# DDR4_SODIMM_PWR.net
KiCad netlist of a schematic drawn in Altium Designer
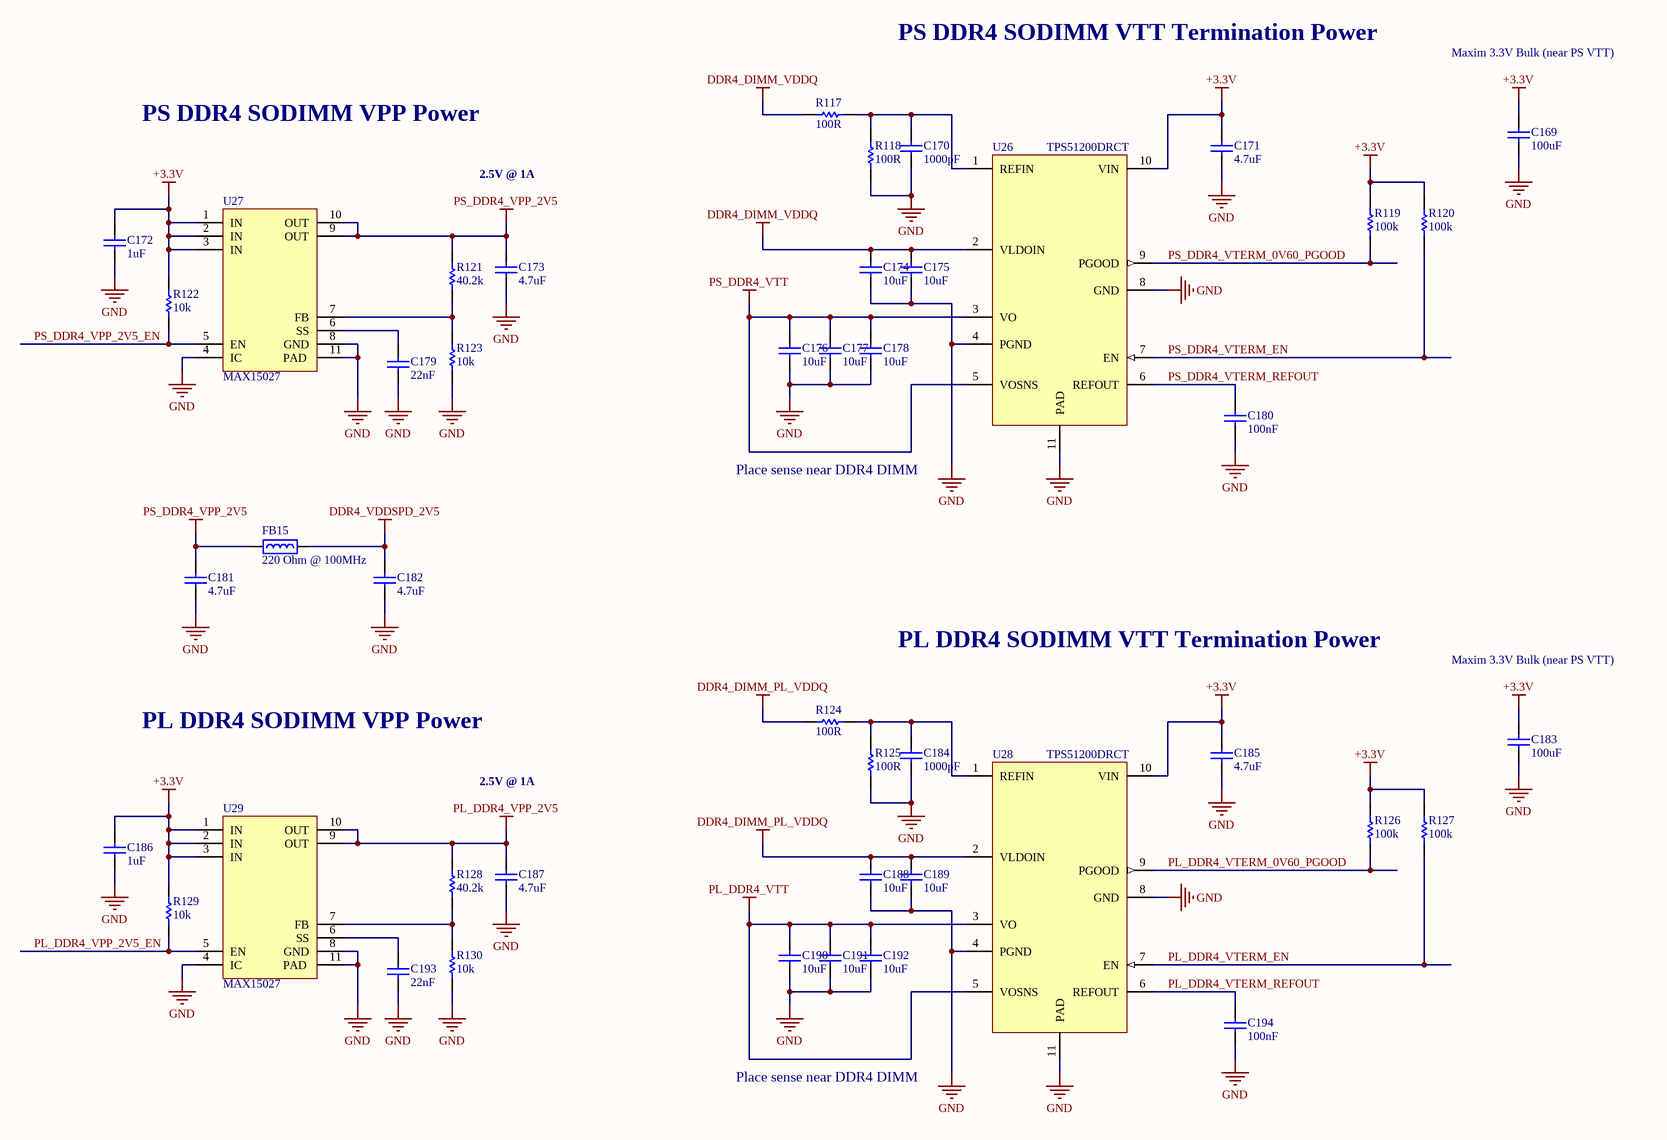
[diagram p0: DDR4_SODIMM_PWR.SchDoc]

(export (version "E")
  (design (tool "Eeschema 10.0.6"))
  (components
    (comp (ref "C169")
      (value "100uF")
      (footprint "CAPC3225N_1210")
      (description "CAP CER 100UF 16V X5R 1210")
      (fields (field (name "VOLTAGE") "16V") (field (name "TOLERANCE") "20%"))
      (libsource (lib "Ultrascale_SchLib") (part "CAPCER1210X5R100U16V_20T"))
    )
    (comp (ref "C170")
      (value "1000pF")
      (footprint "CAPC1005L_0402")
      (description "CAP CER 1000PF 50V X7R 0402")
      (fields (field (name "VOLTAGE") "50V") (field (name "TOLERANCE") "10%"))
      (libsource (lib "Ultrascale_SchLib") (part "CAPCER0402X7R1000P50V_10T"))
    )
    (comp (ref "C171")
      (value "4.7uF")
      (footprint "CAPC1005L_0402")
      (description "CAP CER 4.7UF 10V X5R 0402")
      (fields (field (name "VOLTAGE") "10V") (field (name "TOLERANCE") "10%"))
      (libsource (lib "Ultrascale_SchLib") (part "CAPCER0402X5R4U710V_10T"))
    )
    (comp (ref "C172")
      (value "1uF")
      (footprint "CAPC1005L_0402")
      (description "CAP CER 1UF 16V X5R 0402")
      (fields (field (name "VOLTAGE") "16V") (field (name "TOLERANCE") "20%"))
      (libsource (lib "Ultrascale_SchLib") (part "CAPCER0402X5R1U16V_20T"))
    )
    (comp (ref "C173")
      (value "4.7uF")
      (footprint "CAPC1005L_0402")
      (description "CAP CER 4.7UF 10V X5R 0402")
      (fields (field (name "VOLTAGE") "10V") (field (name "TOLERANCE") "10%"))
      (libsource (lib "Ultrascale_SchLib") (part "CAPCER0402X5R4U710V_10T"))
    )
    (comp (ref "C174")
      (value "10uF")
      (footprint "CAPC1005L_0402")
      (description "CAP CER 10UF 10V X5R 0402")
      (fields (field (name "VOLTAGE") "10V") (field (name "TOLERANCE") "20%"))
      (libsource (lib "Ultrascale_SchLib") (part "CAPCER0402X5R10U10V_20T"))
    )
    (comp (ref "C175")
      (value "10uF")
      (footprint "CAPC1005L_0402")
      (description "CAP CER 10UF 10V X5R 0402")
      (fields (field (name "VOLTAGE") "10V") (field (name "TOLERANCE") "20%"))
      (libsource (lib "Ultrascale_SchLib") (part "CAPCER0402X5R10U10V_20T"))
    )
    (comp (ref "C176")
      (value "10uF")
      (footprint "CAPC1005L_0402")
      (description "CAP CER 10UF 10V X5R 0402")
      (fields (field (name "VOLTAGE") "10V") (field (name "TOLERANCE") "20%"))
      (libsource (lib "Ultrascale_SchLib") (part "CAPCER0402X5R10U10V_20T"))
    )
    (comp (ref "C177")
      (value "10uF")
      (footprint "CAPC1005L_0402")
      (description "CAP CER 10UF 10V X5R 0402")
      (fields (field (name "VOLTAGE") "10V") (field (name "TOLERANCE") "20%"))
      (libsource (lib "Ultrascale_SchLib") (part "CAPCER0402X5R10U10V_20T"))
    )
    (comp (ref "C178")
      (value "10uF")
      (footprint "CAPC1005L_0402")
      (description "CAP CER 10UF 10V X5R 0402")
      (fields (field (name "VOLTAGE") "10V") (field (name "TOLERANCE") "20%"))
      (libsource (lib "Ultrascale_SchLib") (part "CAPCER0402X5R10U10V_20T"))
    )
    (comp (ref "C179")
      (value "22nF")
      (footprint "CAPC1005L_0402")
      (description "CAP CER 0.022UF 50V X7R 0402")
      (fields (field (name "VOLTAGE") "50V") (field (name "TOLERANCE") "10%"))
      (libsource (lib "Ultrascale_SchLib") (part "CAPCER0402X7R22N50V_10T"))
    )
    (comp (ref "C180")
      (value "100nF")
      (footprint "CAPC1005L_0402")
      (description "CAP CER 0.1UF 25V X7R 0402")
      (fields (field (name "VOLTAGE") "25V") (field (name "TOLERANCE") "10%"))
      (libsource (lib "Ultrascale_SchLib") (part "CAPCER0402X7R100N25V_10T"))
    )
    (comp (ref "C181")
      (value "4.7uF")
      (footprint "CAPC1005L_0402")
      (description "CAP CER 4.7UF 10V X5R 0402")
      (fields (field (name "VOLTAGE") "10V") (field (name "TOLERANCE") "10%"))
      (libsource (lib "Ultrascale_SchLib") (part "CAPCER0402X5R4U710V_10T"))
    )
    (comp (ref "C182")
      (value "4.7uF")
      (footprint "CAPC1005L_0402")
      (description "CAP CER 4.7UF 10V X5R 0402")
      (fields (field (name "VOLTAGE") "10V") (field (name "TOLERANCE") "10%"))
      (libsource (lib "Ultrascale_SchLib") (part "CAPCER0402X5R4U710V_10T"))
    )
    (comp (ref "C183")
      (value "100uF")
      (footprint "CAPC3225N_1210")
      (description "CAP CER 100UF 16V X5R 1210")
      (fields (field (name "VOLTAGE") "16V") (field (name "TOLERANCE") "20%"))
      (libsource (lib "Ultrascale_SchLib") (part "CAPCER1210X5R100U16V_20T"))
    )
    (comp (ref "C184")
      (value "1000pF")
      (footprint "CAPC1005L_0402")
      (description "CAP CER 1000PF 50V X7R 0402")
      (fields (field (name "VOLTAGE") "50V") (field (name "TOLERANCE") "10%"))
      (libsource (lib "Ultrascale_SchLib") (part "CAPCER0402X7R1000P50V_10T"))
    )
    (comp (ref "C185")
      (value "4.7uF")
      (footprint "CAPC1005L_0402")
      (description "CAP CER 4.7UF 10V X5R 0402")
      (fields (field (name "VOLTAGE") "10V") (field (name "TOLERANCE") "10%"))
      (libsource (lib "Ultrascale_SchLib") (part "CAPCER0402X5R4U710V_10T"))
    )
    (comp (ref "C186")
      (value "1uF")
      (footprint "CAPC1005L_0402")
      (description "CAP CER 1UF 16V X5R 0402")
      (fields (field (name "VOLTAGE") "16V") (field (name "TOLERANCE") "20%"))
      (libsource (lib "Ultrascale_SchLib") (part "CAPCER0402X5R1U16V_20T"))
    )
    (comp (ref "C187")
      (value "4.7uF")
      (footprint "CAPC1005L_0402")
      (description "CAP CER 4.7UF 10V X5R 0402")
      (fields (field (name "VOLTAGE") "10V") (field (name "TOLERANCE") "10%"))
      (libsource (lib "Ultrascale_SchLib") (part "CAPCER0402X5R4U710V_10T"))
    )
    (comp (ref "C188")
      (value "10uF")
      (footprint "CAPC1005L_0402")
      (description "CAP CER 10UF 10V X5R 0402")
      (fields (field (name "VOLTAGE") "10V") (field (name "TOLERANCE") "20%"))
      (libsource (lib "Ultrascale_SchLib") (part "CAPCER0402X5R10U10V_20T"))
    )
    (comp (ref "C189")
      (value "10uF")
      (footprint "CAPC1005L_0402")
      (description "CAP CER 10UF 10V X5R 0402")
      (fields (field (name "VOLTAGE") "10V") (field (name "TOLERANCE") "20%"))
      (libsource (lib "Ultrascale_SchLib") (part "CAPCER0402X5R10U10V_20T"))
    )
    (comp (ref "C190")
      (value "10uF")
      (footprint "CAPC1005L_0402")
      (description "CAP CER 10UF 10V X5R 0402")
      (fields (field (name "VOLTAGE") "10V") (field (name "TOLERANCE") "20%"))
      (libsource (lib "Ultrascale_SchLib") (part "CAPCER0402X5R10U10V_20T"))
    )
    (comp (ref "C191")
      (value "10uF")
      (footprint "CAPC1005L_0402")
      (description "CAP CER 10UF 10V X5R 0402")
      (fields (field (name "VOLTAGE") "10V") (field (name "TOLERANCE") "20%"))
      (libsource (lib "Ultrascale_SchLib") (part "CAPCER0402X5R10U10V_20T"))
    )
    (comp (ref "C192")
      (value "10uF")
      (footprint "CAPC1005L_0402")
      (description "CAP CER 10UF 10V X5R 0402")
      (fields (field (name "VOLTAGE") "10V") (field (name "TOLERANCE") "20%"))
      (libsource (lib "Ultrascale_SchLib") (part "CAPCER0402X5R10U10V_20T"))
    )
    (comp (ref "C193")
      (value "22nF")
      (footprint "CAPC1005L_0402")
      (description "CAP CER 0.022UF 50V X7R 0402")
      (fields (field (name "VOLTAGE") "50V") (field (name "TOLERANCE") "10%"))
      (libsource (lib "Ultrascale_SchLib") (part "CAPCER0402X7R22N50V_10T"))
    )
    (comp (ref "C194")
      (value "100nF")
      (footprint "CAPC1005L_0402")
      (description "CAP CER 0.1UF 25V X7R 0402")
      (fields (field (name "VOLTAGE") "25V") (field (name "TOLERANCE") "10%"))
      (libsource (lib "Ultrascale_SchLib") (part "CAPCER0402X7R100N25V_10T"))
    )
    (comp (ref "FB15")
      (value "BEAD0603_220_2A5_40M")
      (footprint "INDC1608N_0603")
      (description "FERRITE BEAD 220 OHM 0603 1LN")
      (fields (field (name "IMPEDANCE @ FREQUENCY") "220 Ohm @ 100MHz"))
      (libsource (lib "Ultrascale_SchLib") (part "BEAD0603_220_2A5_40M"))
    )
    (comp (ref "R117")
      (value "100R")
      (footprint "RESC1005L_0402")
      (description "RES SMD 100 OHM 1% 1/10W 0402")
      (fields (field (name "POWER") "1/10W") (field (name "TOLERANCE") "1%"))
      (libsource (lib "Ultrascale_SchLib") (part "RES0402_100R_0W1_1T"))
    )
    (comp (ref "R118")
      (value "100R")
      (footprint "RESC1005L_0402")
      (description "RES SMD 100 OHM 1% 1/10W 0402")
      (fields (field (name "POWER") "1/10W") (field (name "TOLERANCE") "1%"))
      (libsource (lib "Ultrascale_SchLib") (part "RES0402_100R_0W1_1T"))
    )
    (comp (ref "R119")
      (value "100k")
      (footprint "RESC1005L_0402")
      (description "RES SMD 100K OHM 1% 1/5W 0402")
      (fields (field (name "POWER") "1/5W") (field (name "TOLERANCE") "1%"))
      (libsource (lib "Ultrascale_SchLib") (part "RES0402_100K_0W2_1T"))
    )
    (comp (ref "R120")
      (value "100k")
      (footprint "RESC1005L_0402")
      (description "RES SMD 100K OHM 1% 1/5W 0402")
      (fields (field (name "POWER") "1/5W") (field (name "TOLERANCE") "1%"))
      (libsource (lib "Ultrascale_SchLib") (part "RES0402_100K_0W2_1T"))
    )
    (comp (ref "R121")
      (value "40.2k")
      (footprint "RESC1005L_0402")
      (description "RES SMD 40.2K OHM 1% 1/10W 0402")
      (fields (field (name "POWER") "1/10W") (field (name "TOLERANCE") "1%"))
      (libsource (lib "Ultrascale_SchLib") (part "RES0402_40K2_0W1_1T"))
    )
    (comp (ref "R122")
      (value "10k")
      (footprint "RESC1005L_0402")
      (description "RES SMD 10K OHM 0.5% 1/16W 0402")
      (fields (field (name "POWER") "1/16W") (field (name "TOLERANCE") "0.5%"))
      (libsource (lib "Ultrascale_SchLib") (part "RES0402_10K_0W1_05T"))
    )
    (comp (ref "R123")
      (value "10k")
      (footprint "RESC1005L_0402")
      (description "RES SMD 10K OHM 0.5% 1/16W 0402")
      (fields (field (name "POWER") "1/16W") (field (name "TOLERANCE") "0.5%"))
      (libsource (lib "Ultrascale_SchLib") (part "RES0402_10K_0W1_05T"))
    )
    (comp (ref "R124")
      (value "100R")
      (footprint "RESC1005L_0402")
      (description "RES SMD 100 OHM 1% 1/10W 0402")
      (fields (field (name "POWER") "1/10W") (field (name "TOLERANCE") "1%"))
      (libsource (lib "Ultrascale_SchLib") (part "RES0402_100R_0W1_1T"))
    )
    (comp (ref "R125")
      (value "100R")
      (footprint "RESC1005L_0402")
      (description "RES SMD 100 OHM 1% 1/10W 0402")
      (fields (field (name "POWER") "1/10W") (field (name "TOLERANCE") "1%"))
      (libsource (lib "Ultrascale_SchLib") (part "RES0402_100R_0W1_1T"))
    )
    (comp (ref "R126")
      (value "100k")
      (footprint "RESC1005L_0402")
      (description "RES SMD 100K OHM 1% 1/5W 0402")
      (fields (field (name "POWER") "1/5W") (field (name "TOLERANCE") "1%"))
      (libsource (lib "Ultrascale_SchLib") (part "RES0402_100K_0W2_1T"))
    )
    (comp (ref "R127")
      (value "100k")
      (footprint "RESC1005L_0402")
      (description "RES SMD 100K OHM 1% 1/5W 0402")
      (fields (field (name "POWER") "1/5W") (field (name "TOLERANCE") "1%"))
      (libsource (lib "Ultrascale_SchLib") (part "RES0402_100K_0W2_1T"))
    )
    (comp (ref "R128")
      (value "40.2k")
      (footprint "RESC1005L_0402")
      (description "RES SMD 40.2K OHM 1% 1/10W 0402")
      (fields (field (name "POWER") "1/10W") (field (name "TOLERANCE") "1%"))
      (libsource (lib "Ultrascale_SchLib") (part "RES0402_40K2_0W1_1T"))
    )
    (comp (ref "R129")
      (value "10k")
      (footprint "RESC1005L_0402")
      (description "RES SMD 10K OHM 0.5% 1/16W 0402")
      (fields (field (name "POWER") "1/16W") (field (name "TOLERANCE") "0.5%"))
      (libsource (lib "Ultrascale_SchLib") (part "RES0402_10K_0W1_05T"))
    )
    (comp (ref "R130")
      (value "10k")
      (footprint "RESC1005L_0402")
      (description "RES SMD 10K OHM 0.5% 1/16W 0402")
      (fields (field (name "POWER") "1/16W") (field (name "TOLERANCE") "0.5%"))
      (libsource (lib "Ultrascale_SchLib") (part "RES0402_10K_0W1_05T"))
    )
    (comp (ref "U26")
      (value "TPS51200DRCT")
      (footprint "DRC_S-PVSON-N10")
      (description "IC SINK/SOURCE DDR REG 10-SON")
      (libsource (lib "Ultrascale_SchLib") (part "TPS51200DRCT"))
    )
    (comp (ref "U27")
      (value "MAX15027")
      (footprint "MAX15027_T1033+1_V")
      (description "IC REG LINEAR POS ADJ 1A 10TDFN")
      (libsource (lib "Ultrascale_SchLib") (part "MAX15027"))
    )
    (comp (ref "U28")
      (value "TPS51200DRCT")
      (footprint "DRC_S-PVSON-N10")
      (description "IC SINK/SOURCE DDR REG 10-SON")
      (libsource (lib "Ultrascale_SchLib") (part "TPS51200DRCT"))
    )
    (comp (ref "U29")
      (value "MAX15027")
      (footprint "MAX15027_T1033+1_V")
      (description "IC REG LINEAR POS ADJ 1A 10TDFN")
      (libsource (lib "Ultrascale_SchLib") (part "MAX15027"))
    )
  )
  (nets
    (net (code "1") (name "+3.3V") (class "Default")
      (node (ref "C169") (pin "2") (pinfunction "2_2") (pintype "passive"))
      (node (ref "C171") (pin "2") (pinfunction "2_2") (pintype "passive"))
      (node (ref "C172") (pin "2") (pinfunction "2_2") (pintype "passive"))
      (node (ref "C183") (pin "2") (pinfunction "2_2") (pintype "passive"))
      (node (ref "C185") (pin "2") (pinfunction "2_2") (pintype "passive"))
      (node (ref "C186") (pin "2") (pinfunction "2_2") (pintype "passive"))
      (node (ref "R119") (pin "2") (pinfunction "2_2") (pintype "passive"))
      (node (ref "R120") (pin "2") (pinfunction "2_2") (pintype "passive"))
      (node (ref "R122") (pin "2") (pinfunction "2_2") (pintype "passive"))
      (node (ref "R126") (pin "2") (pinfunction "2_2") (pintype "passive"))
      (node (ref "R127") (pin "2") (pinfunction "2_2") (pintype "passive"))
      (node (ref "R129") (pin "2") (pinfunction "2_2") (pintype "passive"))
      (node (ref "U26") (pin "10") (pinfunction "VIN_10") (pintype "passive"))
      (node (ref "U27") (pin "1") (pinfunction "IN_1") (pintype "passive"))
      (node (ref "U27") (pin "2") (pinfunction "IN_2") (pintype "passive"))
      (node (ref "U27") (pin "3") (pinfunction "IN_3") (pintype "passive"))
      (node (ref "U28") (pin "10") (pinfunction "VIN_10") (pintype "passive"))
      (node (ref "U29") (pin "1") (pinfunction "IN_1") (pintype "passive"))
      (node (ref "U29") (pin "2") (pinfunction "IN_2") (pintype "passive"))
      (node (ref "U29") (pin "3") (pinfunction "IN_3") (pintype "passive"))
    )
    (net (code "2") (name "/PL_DDR4_VPP_2V5_EN") (class "Default")
      (node (ref "R129") (pin "1") (pinfunction "1_1") (pintype "passive"))
      (node (ref "U29") (pin "5") (pinfunction "EN_5") (pintype "passive"))
    )
    (net (code "3") (name "/PL_DDR4_VTERM_0V60_PGOOD") (class "Default")
      (node (ref "R126") (pin "1") (pinfunction "1_1") (pintype "passive"))
      (node (ref "U28") (pin "9") (pinfunction "PGOOD_9") (pintype "output"))
    )
    (net (code "4") (name "/PL_DDR4_VTERM_EN") (class "Default")
      (node (ref "R127") (pin "1") (pinfunction "1_1") (pintype "passive"))
      (node (ref "U28") (pin "7") (pinfunction "EN_7") (pintype "input"))
    )
    (net (code "5") (name "/PL_DDR4_VTERM_REFOUT") (class "Default")
      (node (ref "C194") (pin "2") (pinfunction "2_2") (pintype "passive"))
      (node (ref "U28") (pin "6") (pinfunction "REFOUT_6") (pintype "passive"))
    )
    (net (code "6") (name "/PS_DDR4_VPP_2V5_EN") (class "Default")
      (node (ref "R122") (pin "1") (pinfunction "1_1") (pintype "passive"))
      (node (ref "U27") (pin "5") (pinfunction "EN_5") (pintype "passive"))
    )
    (net (code "7") (name "/PS_DDR4_VTERM_0V60_PGOOD") (class "Default")
      (node (ref "R119") (pin "1") (pinfunction "1_1") (pintype "passive"))
      (node (ref "U26") (pin "9") (pinfunction "PGOOD_9") (pintype "output"))
    )
    (net (code "8") (name "/PS_DDR4_VTERM_EN") (class "Default")
      (node (ref "R120") (pin "1") (pinfunction "1_1") (pintype "passive"))
      (node (ref "U26") (pin "7") (pinfunction "EN_7") (pintype "input"))
    )
    (net (code "9") (name "/PS_DDR4_VTERM_REFOUT") (class "Default")
      (node (ref "C180") (pin "2") (pinfunction "2_2") (pintype "passive"))
      (node (ref "U26") (pin "6") (pinfunction "REFOUT_6") (pintype "passive"))
    )
    (net (code "10") (name "DDR4_DIMM_PL_VDDQ") (class "Default")
      (node (ref "C188") (pin "2") (pinfunction "2_2") (pintype "passive"))
      (node (ref "C189") (pin "2") (pinfunction "2_2") (pintype "passive"))
      (node (ref "R124") (pin "2") (pinfunction "2_2") (pintype "passive"))
      (node (ref "U28") (pin "2") (pinfunction "VLDOIN_2") (pintype "passive"))
    )
    (net (code "11") (name "DDR4_DIMM_VDDQ") (class "Default")
      (node (ref "C174") (pin "2") (pinfunction "2_2") (pintype "passive"))
      (node (ref "C175") (pin "2") (pinfunction "2_2") (pintype "passive"))
      (node (ref "R117") (pin "2") (pinfunction "2_2") (pintype "passive"))
      (node (ref "U26") (pin "2") (pinfunction "VLDOIN_2") (pintype "passive"))
    )
    (net (code "12") (name "DDR4_VDDSPD_2V5") (class "Default")
      (node (ref "C182") (pin "2") (pinfunction "2_2") (pintype "passive"))
      (node (ref "FB15") (pin "2") (pinfunction "2_2") (pintype "passive"))
    )
    (net (code "13") (name "GND") (class "Default")
      (node (ref "C169") (pin "1") (pinfunction "1_1") (pintype "passive"))
      (node (ref "C170") (pin "1") (pinfunction "1_1") (pintype "passive"))
      (node (ref "C171") (pin "1") (pinfunction "1_1") (pintype "passive"))
      (node (ref "C172") (pin "1") (pinfunction "1_1") (pintype "passive"))
      (node (ref "C173") (pin "1") (pinfunction "1_1") (pintype "passive"))
      (node (ref "C174") (pin "1") (pinfunction "1_1") (pintype "passive"))
      (node (ref "C175") (pin "1") (pinfunction "1_1") (pintype "passive"))
      (node (ref "C176") (pin "1") (pinfunction "1_1") (pintype "passive"))
      (node (ref "C177") (pin "1") (pinfunction "1_1") (pintype "passive"))
      (node (ref "C178") (pin "1") (pinfunction "1_1") (pintype "passive"))
      (node (ref "C179") (pin "1") (pinfunction "1_1") (pintype "passive"))
      (node (ref "C180") (pin "1") (pinfunction "1_1") (pintype "passive"))
      (node (ref "C181") (pin "1") (pinfunction "1_1") (pintype "passive"))
      (node (ref "C182") (pin "1") (pinfunction "1_1") (pintype "passive"))
      (node (ref "C183") (pin "1") (pinfunction "1_1") (pintype "passive"))
      (node (ref "C184") (pin "1") (pinfunction "1_1") (pintype "passive"))
      (node (ref "C185") (pin "1") (pinfunction "1_1") (pintype "passive"))
      (node (ref "C186") (pin "1") (pinfunction "1_1") (pintype "passive"))
      (node (ref "C187") (pin "1") (pinfunction "1_1") (pintype "passive"))
      (node (ref "C188") (pin "1") (pinfunction "1_1") (pintype "passive"))
      (node (ref "C189") (pin "1") (pinfunction "1_1") (pintype "passive"))
      (node (ref "C190") (pin "1") (pinfunction "1_1") (pintype "passive"))
      (node (ref "C191") (pin "1") (pinfunction "1_1") (pintype "passive"))
      (node (ref "C192") (pin "1") (pinfunction "1_1") (pintype "passive"))
      (node (ref "C193") (pin "1") (pinfunction "1_1") (pintype "passive"))
      (node (ref "C194") (pin "1") (pinfunction "1_1") (pintype "passive"))
      (node (ref "R118") (pin "2") (pinfunction "2_2") (pintype "passive"))
      (node (ref "R123") (pin "1") (pinfunction "1_1") (pintype "passive"))
      (node (ref "R125") (pin "2") (pinfunction "2_2") (pintype "passive"))
      (node (ref "R130") (pin "1") (pinfunction "1_1") (pintype "passive"))
      (node (ref "U26") (pin "11") (pinfunction "PAD_11") (pintype "passive"))
      (node (ref "U26") (pin "4") (pinfunction "PGND_4") (pintype "passive"))
      (node (ref "U26") (pin "8") (pinfunction "GND_8") (pintype "passive"))
      (node (ref "U27") (pin "11") (pinfunction "PAD_11") (pintype "passive"))
      (node (ref "U27") (pin "4") (pinfunction "IC_4") (pintype "passive"))
      (node (ref "U27") (pin "8") (pinfunction "GND_8") (pintype "passive"))
      (node (ref "U28") (pin "11") (pinfunction "PAD_11") (pintype "passive"))
      (node (ref "U28") (pin "4") (pinfunction "PGND_4") (pintype "passive"))
      (node (ref "U28") (pin "8") (pinfunction "GND_8") (pintype "passive"))
      (node (ref "U29") (pin "11") (pinfunction "PAD_11") (pintype "passive"))
      (node (ref "U29") (pin "4") (pinfunction "IC_4") (pintype "passive"))
      (node (ref "U29") (pin "8") (pinfunction "GND_8") (pintype "passive"))
    )
    (net (code "14") (name "Net-(U26-REFIN)") (class "Default")
      (node (ref "C170") (pin "2") (pinfunction "2_2") (pintype "passive"))
      (node (ref "R117") (pin "1") (pinfunction "1_1") (pintype "passive"))
      (node (ref "R118") (pin "1") (pinfunction "1_1") (pintype "passive"))
      (node (ref "U26") (pin "1") (pinfunction "REFIN_1") (pintype "passive"))
    )
    (net (code "15") (name "Net-(U27-FB)") (class "Default")
      (node (ref "R121") (pin "1") (pinfunction "1_1") (pintype "passive"))
      (node (ref "R123") (pin "2") (pinfunction "2_2") (pintype "passive"))
      (node (ref "U27") (pin "7") (pinfunction "FB_7") (pintype "passive"))
    )
    (net (code "16") (name "Net-(U27-SS)") (class "Default")
      (node (ref "C179") (pin "2") (pinfunction "2_2") (pintype "passive"))
      (node (ref "U27") (pin "6") (pinfunction "SS_6") (pintype "passive"))
    )
    (net (code "17") (name "Net-(U28-REFIN)") (class "Default")
      (node (ref "C184") (pin "2") (pinfunction "2_2") (pintype "passive"))
      (node (ref "R124") (pin "1") (pinfunction "1_1") (pintype "passive"))
      (node (ref "R125") (pin "1") (pinfunction "1_1") (pintype "passive"))
      (node (ref "U28") (pin "1") (pinfunction "REFIN_1") (pintype "passive"))
    )
    (net (code "18") (name "Net-(U29-FB)") (class "Default")
      (node (ref "R128") (pin "1") (pinfunction "1_1") (pintype "passive"))
      (node (ref "R130") (pin "2") (pinfunction "2_2") (pintype "passive"))
      (node (ref "U29") (pin "7") (pinfunction "FB_7") (pintype "passive"))
    )
    (net (code "19") (name "Net-(U29-SS)") (class "Default")
      (node (ref "C193") (pin "2") (pinfunction "2_2") (pintype "passive"))
      (node (ref "U29") (pin "6") (pinfunction "SS_6") (pintype "passive"))
    )
    (net (code "20") (name "PL_DDR4_VPP_2V5") (class "Default")
      (node (ref "C187") (pin "2") (pinfunction "2_2") (pintype "passive"))
      (node (ref "R128") (pin "2") (pinfunction "2_2") (pintype "passive"))
      (node (ref "U29") (pin "10") (pinfunction "OUT_10") (pintype "passive"))
      (node (ref "U29") (pin "9") (pinfunction "OUT_9") (pintype "passive"))
    )
    (net (code "21") (name "PL_DDR4_VTT") (class "Default")
      (node (ref "C190") (pin "2") (pinfunction "2_2") (pintype "passive"))
      (node (ref "C191") (pin "2") (pinfunction "2_2") (pintype "passive"))
      (node (ref "C192") (pin "2") (pinfunction "2_2") (pintype "passive"))
      (node (ref "U28") (pin "3") (pinfunction "VO_3") (pintype "passive"))
      (node (ref "U28") (pin "5") (pinfunction "VOSNS_5") (pintype "passive"))
    )
    (net (code "22") (name "PS_DDR4_VPP_2V5") (class "Default")
      (node (ref "C173") (pin "2") (pinfunction "2_2") (pintype "passive"))
      (node (ref "C181") (pin "2") (pinfunction "2_2") (pintype "passive"))
      (node (ref "FB15") (pin "1") (pinfunction "1_1") (pintype "passive"))
      (node (ref "R121") (pin "2") (pinfunction "2_2") (pintype "passive"))
      (node (ref "U27") (pin "10") (pinfunction "OUT_10") (pintype "passive"))
      (node (ref "U27") (pin "9") (pinfunction "OUT_9") (pintype "passive"))
    )
    (net (code "23") (name "PS_DDR4_VTT") (class "Default")
      (node (ref "C176") (pin "2") (pinfunction "2_2") (pintype "passive"))
      (node (ref "C177") (pin "2") (pinfunction "2_2") (pintype "passive"))
      (node (ref "C178") (pin "2") (pinfunction "2_2") (pintype "passive"))
      (node (ref "U26") (pin "3") (pinfunction "VO_3") (pintype "passive"))
      (node (ref "U26") (pin "5") (pinfunction "VOSNS_5") (pintype "passive"))
    )
  )
)
